# fallBz.net
KiCad netlist of a schematic drawn in EAGLE
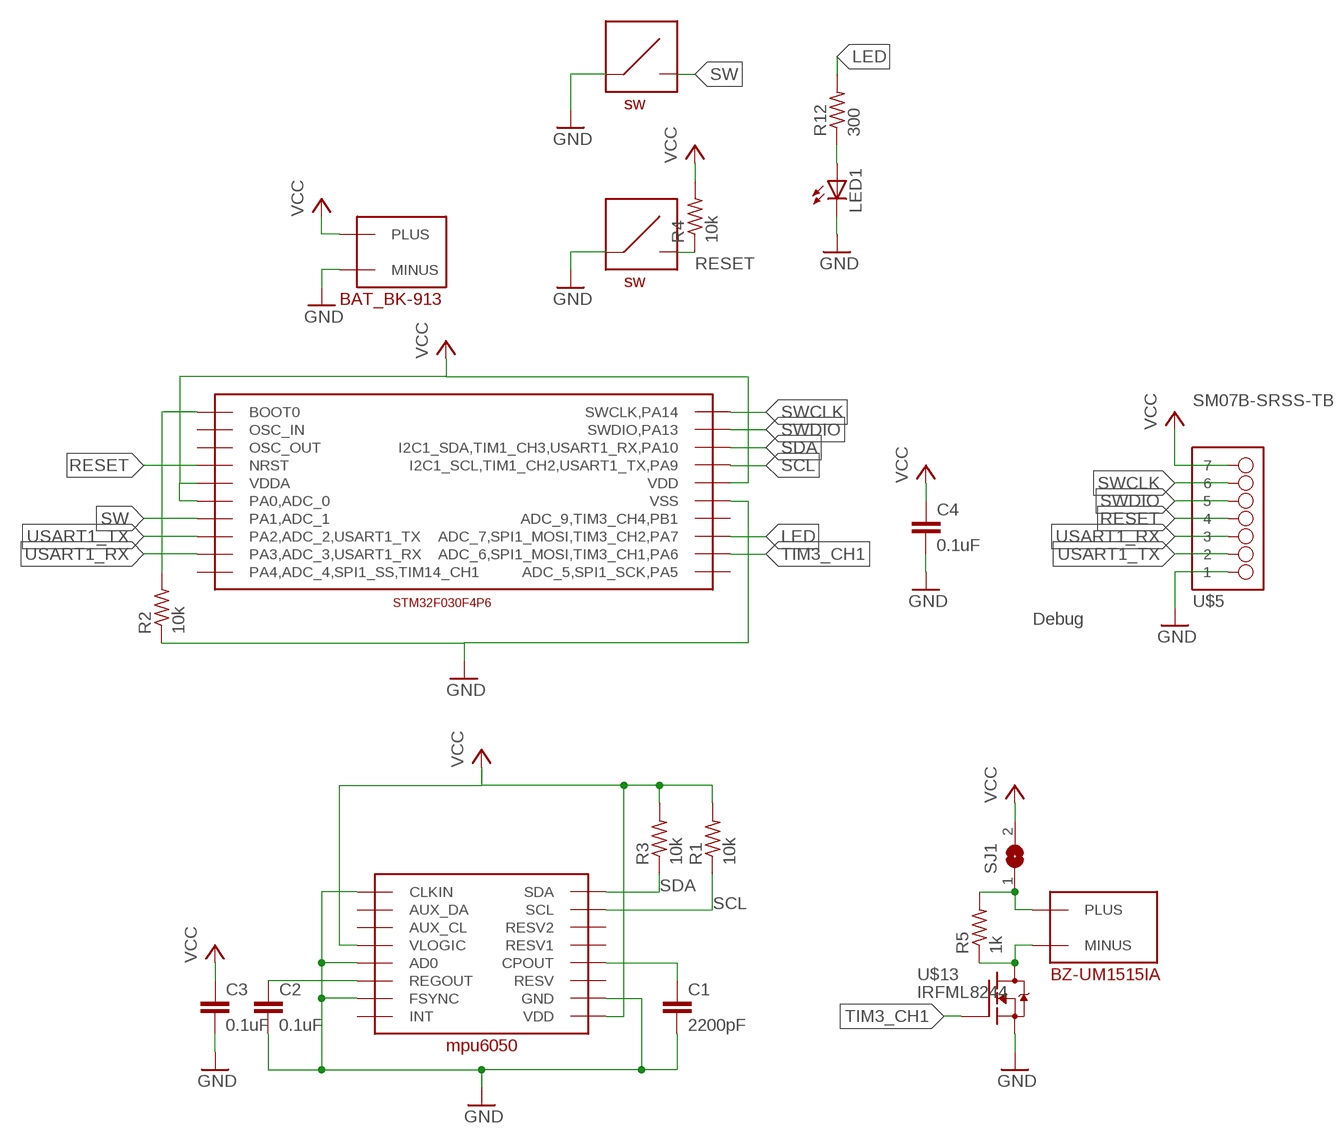
[diagram p0: schematic, sheet 1]

(export (version "E")
  (design (tool "Eeschema 10.0.6"))
  (components
    (comp (ref "C1")
      (value "2200pF")
      (footprint "eagle-import:C0603K")
      (libsource (lib "eagle-import") (part "C-EUC0603K"))
    )
    (comp (ref "C2")
      (value "0.1uF")
      (footprint "eagle-import:C0603K")
      (libsource (lib "eagle-import") (part "C-EUC0603K"))
    )
    (comp (ref "C3")
      (value "0.1uF")
      (footprint "eagle-import:C0603K")
      (libsource (lib "eagle-import") (part "C-EUC0603K"))
    )
    (comp (ref "C4")
      (value "0.1uF")
      (footprint "eagle-import:C0603K")
      (libsource (lib "eagle-import") (part "C-EUC0603K"))
    )
    (comp (ref "GH")
      (value "BAT_BK-913")
      (footprint "eagle-import:BAT_BK-913")
      (libsource (lib "eagle-import") (part "BAT_BK-913"))
    )
    (comp (ref "LED1")
      (value "LEDCHIP-LED0603")
      (footprint "eagle-import:CHIP-LED0603")
      (libsource (lib "eagle-import") (part "LEDCHIP-LED0603"))
    )
    (comp (ref "R1")
      (value "10k")
      (footprint "eagle-import:R0603")
      (libsource (lib "eagle-import") (part "R-US_R0603"))
    )
    (comp (ref "R2")
      (value "10k")
      (footprint "eagle-import:R0603")
      (libsource (lib "eagle-import") (part "R-US_R0603"))
    )
    (comp (ref "R3")
      (value "10k")
      (footprint "eagle-import:R0603")
      (libsource (lib "eagle-import") (part "R-US_R0603"))
    )
    (comp (ref "R4")
      (value "10k")
      (footprint "eagle-import:R0603")
      (libsource (lib "eagle-import") (part "R-US_R0603"))
    )
    (comp (ref "R5")
      (value "1k")
      (footprint "eagle-import:R0603")
      (libsource (lib "eagle-import") (part "R-US_R0603"))
    )
    (comp (ref "R12")
      (value "300")
      (footprint "eagle-import:R0603")
      (libsource (lib "eagle-import") (part "R-US_R0603"))
    )
    (comp (ref "SJ1") (value "SJ") (footprint "eagle-import:SJ") (libsource (lib "eagle-import") (part "SJ")))
    (comp (ref "U$1")
      (value "STM-TSSOP20")
      (footprint "eagle-import:STM-TSSOP20")
      (libsource (lib "eagle-import") (part "STM-TSSOP20"))
    )
    (comp (ref "U$2")
      (value "BZ-UM1515IA")
      (footprint "eagle-import:BZ-UM1515IA")
      (libsource (lib "eagle-import") (part "BZ-UM1515IA"))
    )
    (comp (ref "U$3")
      (value "MPU6050")
      (footprint "eagle-import:MPU6050")
      (libsource (lib "eagle-import") (part "MPU6050"))
    )
    (comp (ref "U$4")
      (value "KMT071-NGJ-LHS")
      (footprint "eagle-import:KMT071-NGJ-LHS")
      (libsource (lib "eagle-import") (part "KMT071-NGJ-LHS"))
    )
    (comp (ref "U$5")
      (value "SM07B-SRSS-TB")
      (footprint "eagle-import:SM07B-SRSS-TB")
      (libsource (lib "eagle-import") (part "SM07B-SRSS-TB"))
    )
    (comp (ref "U$7")
      (value "KMT071-NGJ-LHS")
      (footprint "eagle-import:KMT071-NGJ-LHS")
      (libsource (lib "eagle-import") (part "KMT071-NGJ-LHS"))
    )
    (comp (ref "U$13")
      (value "IRFML8244")
      (footprint "eagle-import:SOT23")
      (libsource (lib "eagle-import") (part "IRFML8244"))
    )
  )
  (nets
    (net (code "1") (name "GND") (class "Default")
      (node (ref "C1") (pin "2") (pinfunction "2_2") (pintype "passive"))
      (node (ref "C2") (pin "2") (pinfunction "2_2") (pintype "passive"))
      (node (ref "C3") (pin "2") (pinfunction "2_2") (pintype "passive"))
      (node (ref "C4") (pin "2") (pinfunction "2_2") (pintype "passive"))
      (node (ref "GH") (pin "MINUS") (pinfunction "MINUS_MINUS") (pintype "bidirectional"))
      (node (ref "LED1") (pin "C") (pinfunction "C_C") (pintype "passive"))
      (node (ref "R2") (pin "1") (pinfunction "1_1") (pintype "passive"))
      (node (ref "U$1") (pin "P$15") (pinfunction "VSS_P$15") (pintype "bidirectional"))
      (node (ref "U$13") (pin "2") (pinfunction "S_2") (pintype "passive"))
      (node (ref "U$3") (pin "AD0") (pinfunction "AD0_AD0") (pintype "bidirectional"))
      (node (ref "U$3") (pin "CLKIN") (pinfunction "CLKIN_CLKIN") (pintype "bidirectional"))
      (node (ref "U$3") (pin "FSYNC") (pinfunction "FSYNC_FSYNC") (pintype "bidirectional"))
      (node (ref "U$3") (pin "GND") (pinfunction "GND_GND") (pintype "bidirectional"))
      (node (ref "U$4") (pin "SW0") (pinfunction "P$1_SW0") (pintype "bidirectional"))
      (node (ref "U$4") (pin "SW00") (pinfunction "P$1_SW00") (pintype "bidirectional"))
      (node (ref "U$5") (pin "P$1") (pinfunction "1_P$1") (pintype "bidirectional"))
      (node (ref "U$7") (pin "SW0") (pinfunction "P$1_SW0") (pintype "bidirectional"))
      (node (ref "U$7") (pin "SW00") (pinfunction "P$1_SW00") (pintype "bidirectional"))
    )
    (net (code "2") (name "LED") (class "Default")
      (node (ref "R12") (pin "2") (pinfunction "2_2") (pintype "passive"))
      (node (ref "U$1") (pin "P$13") (pinfunction "ADC_7,SPI1_MOSI,TIM3_CH2,PA7_P$13") (pintype "bidirectional"))
    )
    (net (code "3") (name "Net-(C1-Pad1)") (class "Default")
      (node (ref "C1") (pin "1") (pinfunction "1_1") (pintype "passive"))
      (node (ref "U$3") (pin "CPOUT") (pinfunction "CPOUT_CPOUT") (pintype "bidirectional"))
    )
    (net (code "4") (name "Net-(C2-Pad1)") (class "Default")
      (node (ref "C2") (pin "1") (pinfunction "1_1") (pintype "passive"))
      (node (ref "U$3") (pin "REGOUT") (pinfunction "REGOUT_REGOUT") (pintype "bidirectional"))
    )
    (net (code "5") (name "Net-(LED1-PadA)") (class "Default")
      (node (ref "LED1") (pin "A") (pinfunction "A_A") (pintype "passive"))
      (node (ref "R12") (pin "1") (pinfunction "1_1") (pintype "passive"))
    )
    (net (code "6") (name "Net-(R5-Pad2)") (class "Default")
      (node (ref "R5") (pin "2") (pinfunction "2_2") (pintype "passive"))
      (node (ref "SJ1") (pin "1") (pinfunction "1_1") (pintype "passive"))
      (node (ref "U$2") (pin "PLUS") (pinfunction "PLUS_PLUS") (pintype "bidirectional"))
    )
    (net (code "7") (name "Net-(U$1-BOOT0)") (class "Default")
      (node (ref "R2") (pin "2") (pinfunction "2_2") (pintype "passive"))
      (node (ref "U$1") (pin "P$1") (pinfunction "BOOT0_P$1") (pintype "bidirectional"))
    )
    (net (code "8") (name "Net-(U$13-D)") (class "Default")
      (node (ref "R5") (pin "1") (pinfunction "1_1") (pintype "passive"))
      (node (ref "U$13") (pin "3") (pinfunction "D_3") (pintype "passive"))
      (node (ref "U$2") (pin "MINUS") (pinfunction "MINUS_MINUS") (pintype "bidirectional"))
    )
    (net (code "9") (name "RESET") (class "Default")
      (node (ref "R4") (pin "1") (pinfunction "1_1") (pintype "passive"))
      (node (ref "U$1") (pin "P$4") (pinfunction "NRST_P$4") (pintype "bidirectional"))
      (node (ref "U$5") (pin "P$4") (pinfunction "4_P$4") (pintype "bidirectional"))
      (node (ref "U$7") (pin "SW1") (pinfunction "P$2_SW1") (pintype "bidirectional"))
      (node (ref "U$7") (pin "SW11") (pinfunction "P$2_SW11") (pintype "bidirectional"))
    )
    (net (code "10") (name "SCL") (class "Default")
      (node (ref "R1") (pin "1") (pinfunction "1_1") (pintype "passive"))
      (node (ref "U$1") (pin "P$17") (pinfunction "I2C1_SCL,TIM1_CH2,USART1_TX,PA9_P$17") (pintype "bidirectional"))
      (node (ref "U$3") (pin "SCL") (pinfunction "SCL_SCL") (pintype "bidirectional"))
    )
    (net (code "11") (name "SDA") (class "Default")
      (node (ref "R3") (pin "1") (pinfunction "1_1") (pintype "passive"))
      (node (ref "U$1") (pin "P$18") (pinfunction "I2C1_SDA,TIM1_CH3,USART1_RX,PA10_P$18") (pintype "bidirectional"))
      (node (ref "U$3") (pin "SDA") (pinfunction "SDA_SDA") (pintype "bidirectional"))
    )
    (net (code "12") (name "SW") (class "Default")
      (node (ref "U$1") (pin "P$7") (pinfunction "PA1,ADC_1_P$7") (pintype "bidirectional"))
      (node (ref "U$4") (pin "SW1") (pinfunction "P$2_SW1") (pintype "bidirectional"))
      (node (ref "U$4") (pin "SW11") (pinfunction "P$2_SW11") (pintype "bidirectional"))
    )
    (net (code "13") (name "SWCLK") (class "Default")
      (node (ref "U$1") (pin "P$20") (pinfunction "SWCLK,PA14_P$20") (pintype "bidirectional"))
      (node (ref "U$5") (pin "P$6") (pinfunction "6_P$6") (pintype "bidirectional"))
    )
    (net (code "14") (name "SWDIO") (class "Default")
      (node (ref "U$1") (pin "P$19") (pinfunction "SWDIO,PA13_P$19") (pintype "bidirectional"))
      (node (ref "U$5") (pin "P$5") (pinfunction "5_P$5") (pintype "bidirectional"))
    )
    (net (code "15") (name "TIM3_CH1") (class "Default")
      (node (ref "U$1") (pin "P$12") (pinfunction "ADC_6,SPI1_MOSI,TIM3_CH1,PA6_P$12") (pintype "bidirectional"))
      (node (ref "U$13") (pin "1") (pinfunction "G_1") (pintype "passive"))
    )
    (net (code "16") (name "USART1_RX") (class "Default")
      (node (ref "U$1") (pin "P$9") (pinfunction "PA3,ADC_3,USART1_RX_P$9") (pintype "bidirectional"))
      (node (ref "U$5") (pin "P$3") (pinfunction "3_P$3") (pintype "bidirectional"))
    )
    (net (code "17") (name "USART1_TX") (class "Default")
      (node (ref "U$1") (pin "P$8") (pinfunction "PA2,ADC_2,USART1_TX_P$8") (pintype "bidirectional"))
      (node (ref "U$5") (pin "P$2") (pinfunction "2_P$2") (pintype "bidirectional"))
    )
    (net (code "18") (name "VCC") (class "Default")
      (node (ref "C3") (pin "1") (pinfunction "1_1") (pintype "passive"))
      (node (ref "C4") (pin "1") (pinfunction "1_1") (pintype "passive"))
      (node (ref "GH") (pin "PLUS0") (pinfunction "PLUS_PLUS0") (pintype "bidirectional"))
      (node (ref "GH") (pin "PLUS1") (pinfunction "PLUS_PLUS1") (pintype "bidirectional"))
      (node (ref "R1") (pin "2") (pinfunction "2_2") (pintype "passive"))
      (node (ref "R3") (pin "2") (pinfunction "2_2") (pintype "passive"))
      (node (ref "R4") (pin "2") (pinfunction "2_2") (pintype "passive"))
      (node (ref "SJ1") (pin "2") (pinfunction "2_2") (pintype "passive"))
      (node (ref "U$1") (pin "P$16") (pinfunction "VDD_P$16") (pintype "bidirectional"))
      (node (ref "U$1") (pin "P$5") (pinfunction "VDDA_P$5") (pintype "bidirectional"))
      (node (ref "U$1") (pin "P$6") (pinfunction "PA0,ADC_0_P$6") (pintype "bidirectional"))
      (node (ref "U$3") (pin "VDD") (pinfunction "VDD_VDD") (pintype "bidirectional"))
      (node (ref "U$3") (pin "VLOGIC") (pinfunction "VLOGIC_VLOGIC") (pintype "bidirectional"))
      (node (ref "U$5") (pin "P$7") (pinfunction "7_P$7") (pintype "bidirectional"))
    )
    (net (code "19") (name "unconnected-(U$1-ADC_5,SPI1_SCK,PA5-PadP$11)") (class "Default")
      (node (ref "U$1") (pin "P$11") (pinfunction "ADC_5,SPI1_SCK,PA5_P$11") (pintype "bidirectional"))
    )
    (net (code "20") (name "unconnected-(U$1-ADC_9,TIM3_CH4,PB1-PadP$14)") (class "Default")
      (node (ref "U$1") (pin "P$14") (pinfunction "ADC_9,TIM3_CH4,PB1_P$14") (pintype "bidirectional"))
    )
    (net (code "21") (name "unconnected-(U$1-OSC_IN-PadP$2)") (class "Default")
      (node (ref "U$1") (pin "P$2") (pinfunction "OSC_IN_P$2") (pintype "bidirectional"))
    )
    (net (code "22") (name "unconnected-(U$1-OSC_OUT-PadP$3)") (class "Default")
      (node (ref "U$1") (pin "P$3") (pinfunction "OSC_OUT_P$3") (pintype "bidirectional"))
    )
    (net (code "23") (name "unconnected-(U$1-PA4,ADC_4,SPI1_SS,TIM14_CH1-PadP$10)") (class "Default")
      (node (ref "U$1") (pin "P$10") (pinfunction "PA4,ADC_4,SPI1_SS,TIM14_CH1_P$10") (pintype "bidirectional"))
    )
    (net (code "24") (name "unconnected-(U$3-PadAUX_CL)") (class "Default")
      (node (ref "U$3") (pin "AUX_CL") (pinfunction "AUX_CL_AUX_CL") (pintype "bidirectional"))
    )
    (net (code "25") (name "unconnected-(U$3-PadAUX_DA)") (class "Default")
      (node (ref "U$3") (pin "AUX_DA") (pinfunction "AUX_DA_AUX_DA") (pintype "bidirectional"))
    )
    (net (code "26") (name "unconnected-(U$3-PadINT)") (class "Default")
      (node (ref "U$3") (pin "INT") (pinfunction "INT_INT") (pintype "bidirectional"))
    )
    (net (code "27") (name "unconnected-(U$3-PadRESV)") (class "Default")
      (node (ref "U$3") (pin "RESV") (pinfunction "RESV_RESV") (pintype "bidirectional"))
    )
    (net (code "28") (name "unconnected-(U$3-PadRESV1)") (class "Default")
      (node (ref "U$3") (pin "RESV1") (pinfunction "RESV1_RESV1") (pintype "bidirectional"))
    )
    (net (code "29") (name "unconnected-(U$3-PadRESV2)") (class "Default")
      (node (ref "U$3") (pin "RESV2") (pinfunction "RESV2_RESV2") (pintype "bidirectional"))
    )
  )
)
